# IR_SCOOTER.net
KiCad netlist of a schematic drawn in Altium Designer
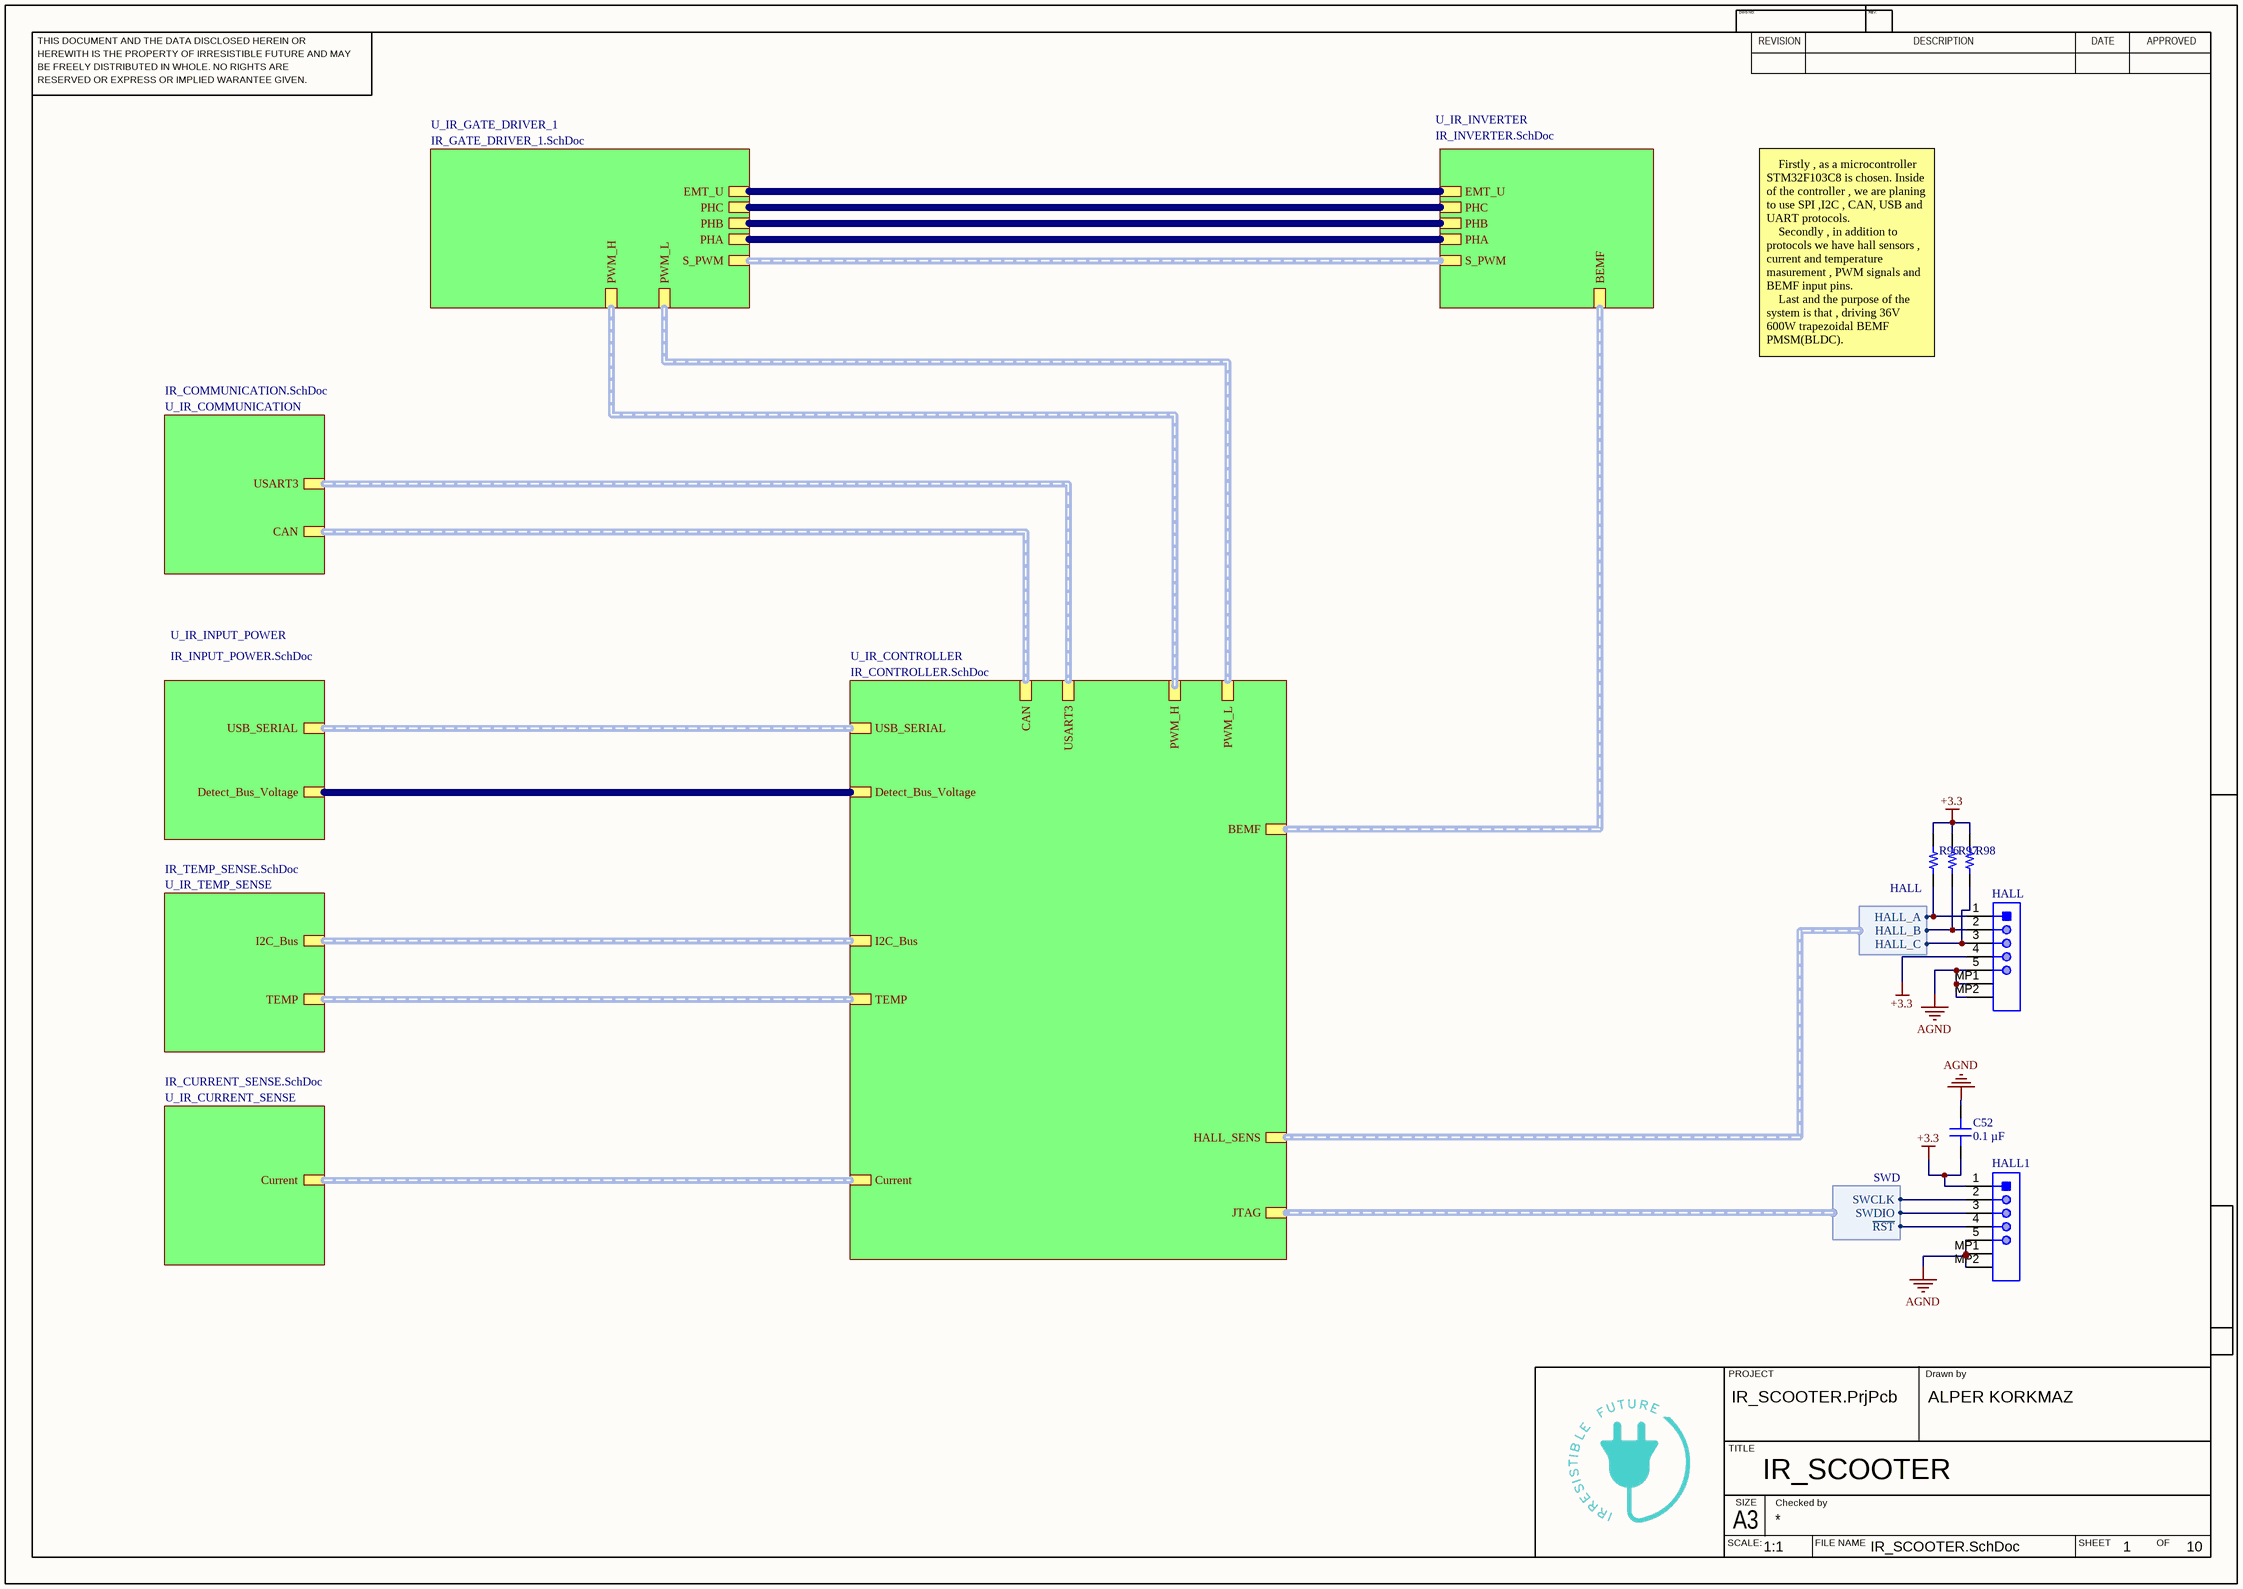
[diagram p0: IR_SCOOTER.SchDoc]

(export (version "E")
  (design (tool "Eeschema 10.0.6"))
  (components
    (comp (ref "C52")
      (value "0.1 µF")
      (footprint "CAP 0805_2012")
      (description "CAP CER 0.1UF 100V X5R 0805")
      (fields (field (name "PART NUMBER") "HMK212BJ104KG-T") (field (name "MANUFACTURER") "Taiyo Yuden"))
      (libsource (lib "Celestial Altium Library - altium_library") (part "Capacitor"))
    )
    (comp (ref "HALL")
      (value "53261-0571")
      (footprint "MOLX-52361-0571-5_V")
      (description "Male Header, Pitch 1.25 mm, 1 x 5 Position, Height 3.4 mm, RoHS, Tape and Reel")
      (fields (field (name "MANUFACTURER") "Molex"))
      (libsource (lib "Altium Content Vault") (part "CN-1P-2M-R5"))
    )
    (comp (ref "HALL1")
      (value "53261-0571")
      (footprint "MOLX-52361-0571-5_V")
      (description "Male Header, Pitch 1.25 mm, 1 x 5 Position, Height 3.4 mm, RoHS, Tape and Reel")
      (fields (field (name "MANUFACTURER") "Molex"))
      (libsource (lib "Altium Content Vault") (part "CN-1P-2M-R5"))
    )
    (comp (ref "R96")
      (value "10 kOhms")
      (footprint "RES 0603_1608")
      (description "RES 10K OHM 0.1% 1/16W 0603")
      (fields
        (field (name "PART NUMBER") "RNCS0603BKE10K0")
        (field (name "MANUFACTURER") "Stackpole Electronics Inc")
      )
      (libsource (lib "Celestial Altium Library - altium_library") (part "Resistor"))
    )
    (comp (ref "R97")
      (value "10 kOhms")
      (footprint "RES 0603_1608")
      (description "RES 10K OHM 0.1% 1/16W 0603")
      (fields
        (field (name "PART NUMBER") "RNCS0603BKE10K0")
        (field (name "MANUFACTURER") "Stackpole Electronics Inc")
      )
      (libsource (lib "Celestial Altium Library - altium_library") (part "Resistor"))
    )
    (comp (ref "R98")
      (value "10 kOhms")
      (footprint "RES 0603_1608")
      (description "RES 10K OHM 0.1% 1/16W 0603")
      (fields
        (field (name "PART NUMBER") "RNCS0603BKE10K0")
        (field (name "MANUFACTURER") "Stackpole Electronics Inc")
      )
      (libsource (lib "Celestial Altium Library - altium_library") (part "Resistor"))
    )
  )
  (nets
    (net (code "3") (name "+3.3") (class "Default")
      (node (ref "C52") (pin "1") (pinfunction "1_1") (pintype "passive"))
      (node (ref "HALL") (pin "4") (pinfunction "4_4") (pintype "passive"))
      (node (ref "HALL1") (pin "1") (pinfunction "1_1") (pintype "passive"))
      (node (ref "R96") (pin "2") (pinfunction "2_2") (pintype "passive"))
      (node (ref "R97") (pin "2") (pinfunction "2_2") (pintype "passive"))
      (node (ref "R98") (pin "2") (pinfunction "2_2") (pintype "passive"))
    )
    (net (code "9") (name "/HALL_A") (class "Default")
      (node (ref "HALL") (pin "1") (pinfunction "1_1") (pintype "passive"))
      (node (ref "R96") (pin "1") (pinfunction "1_1") (pintype "passive"))
    )
    (net (code "10") (name "/HALL_B") (class "Default")
      (node (ref "HALL") (pin "2") (pinfunction "2_2") (pintype "passive"))
      (node (ref "R97") (pin "1") (pinfunction "1_1") (pintype "passive"))
    )
    (net (code "11") (name "/HALL_C") (class "Default")
      (node (ref "HALL") (pin "3") (pinfunction "3_3") (pintype "passive"))
      (node (ref "R98") (pin "1") (pinfunction "1_1") (pintype "passive"))
    )
    (net (code "18") (name "/SWCLK") (class "Default")
      (node (ref "HALL1") (pin "2") (pinfunction "2_2") (pintype "passive"))
    )
    (net (code "19") (name "/SWDIO") (class "Default")
      (node (ref "HALL1") (pin "3") (pinfunction "3_3") (pintype "passive"))
    )
    (net (code "26") (name "/~{RST}") (class "Default")
      (node (ref "HALL1") (pin "4") (pinfunction "4_4") (pintype "passive"))
    )
    (net (code "27") (name "AGND") (class "Default")
      (node (ref "C52") (pin "2") (pinfunction "2_2") (pintype "passive"))
      (node (ref "HALL") (pin "5") (pinfunction "5_5") (pintype "passive"))
      (node (ref "HALL") (pin "MP1") (pinfunction "MP1_MP1") (pintype "passive"))
      (node (ref "HALL") (pin "MP2") (pinfunction "MP2_MP2") (pintype "passive"))
      (node (ref "HALL1") (pin "5") (pinfunction "5_5") (pintype "passive"))
      (node (ref "HALL1") (pin "MP1") (pinfunction "MP1_MP1") (pintype "passive"))
      (node (ref "HALL1") (pin "MP2") (pinfunction "MP2_MP2") (pintype "passive"))
    )
  )
)
